# control_prg_01_10_2018.net
KiCad netlist of a schematic drawn in EAGLE
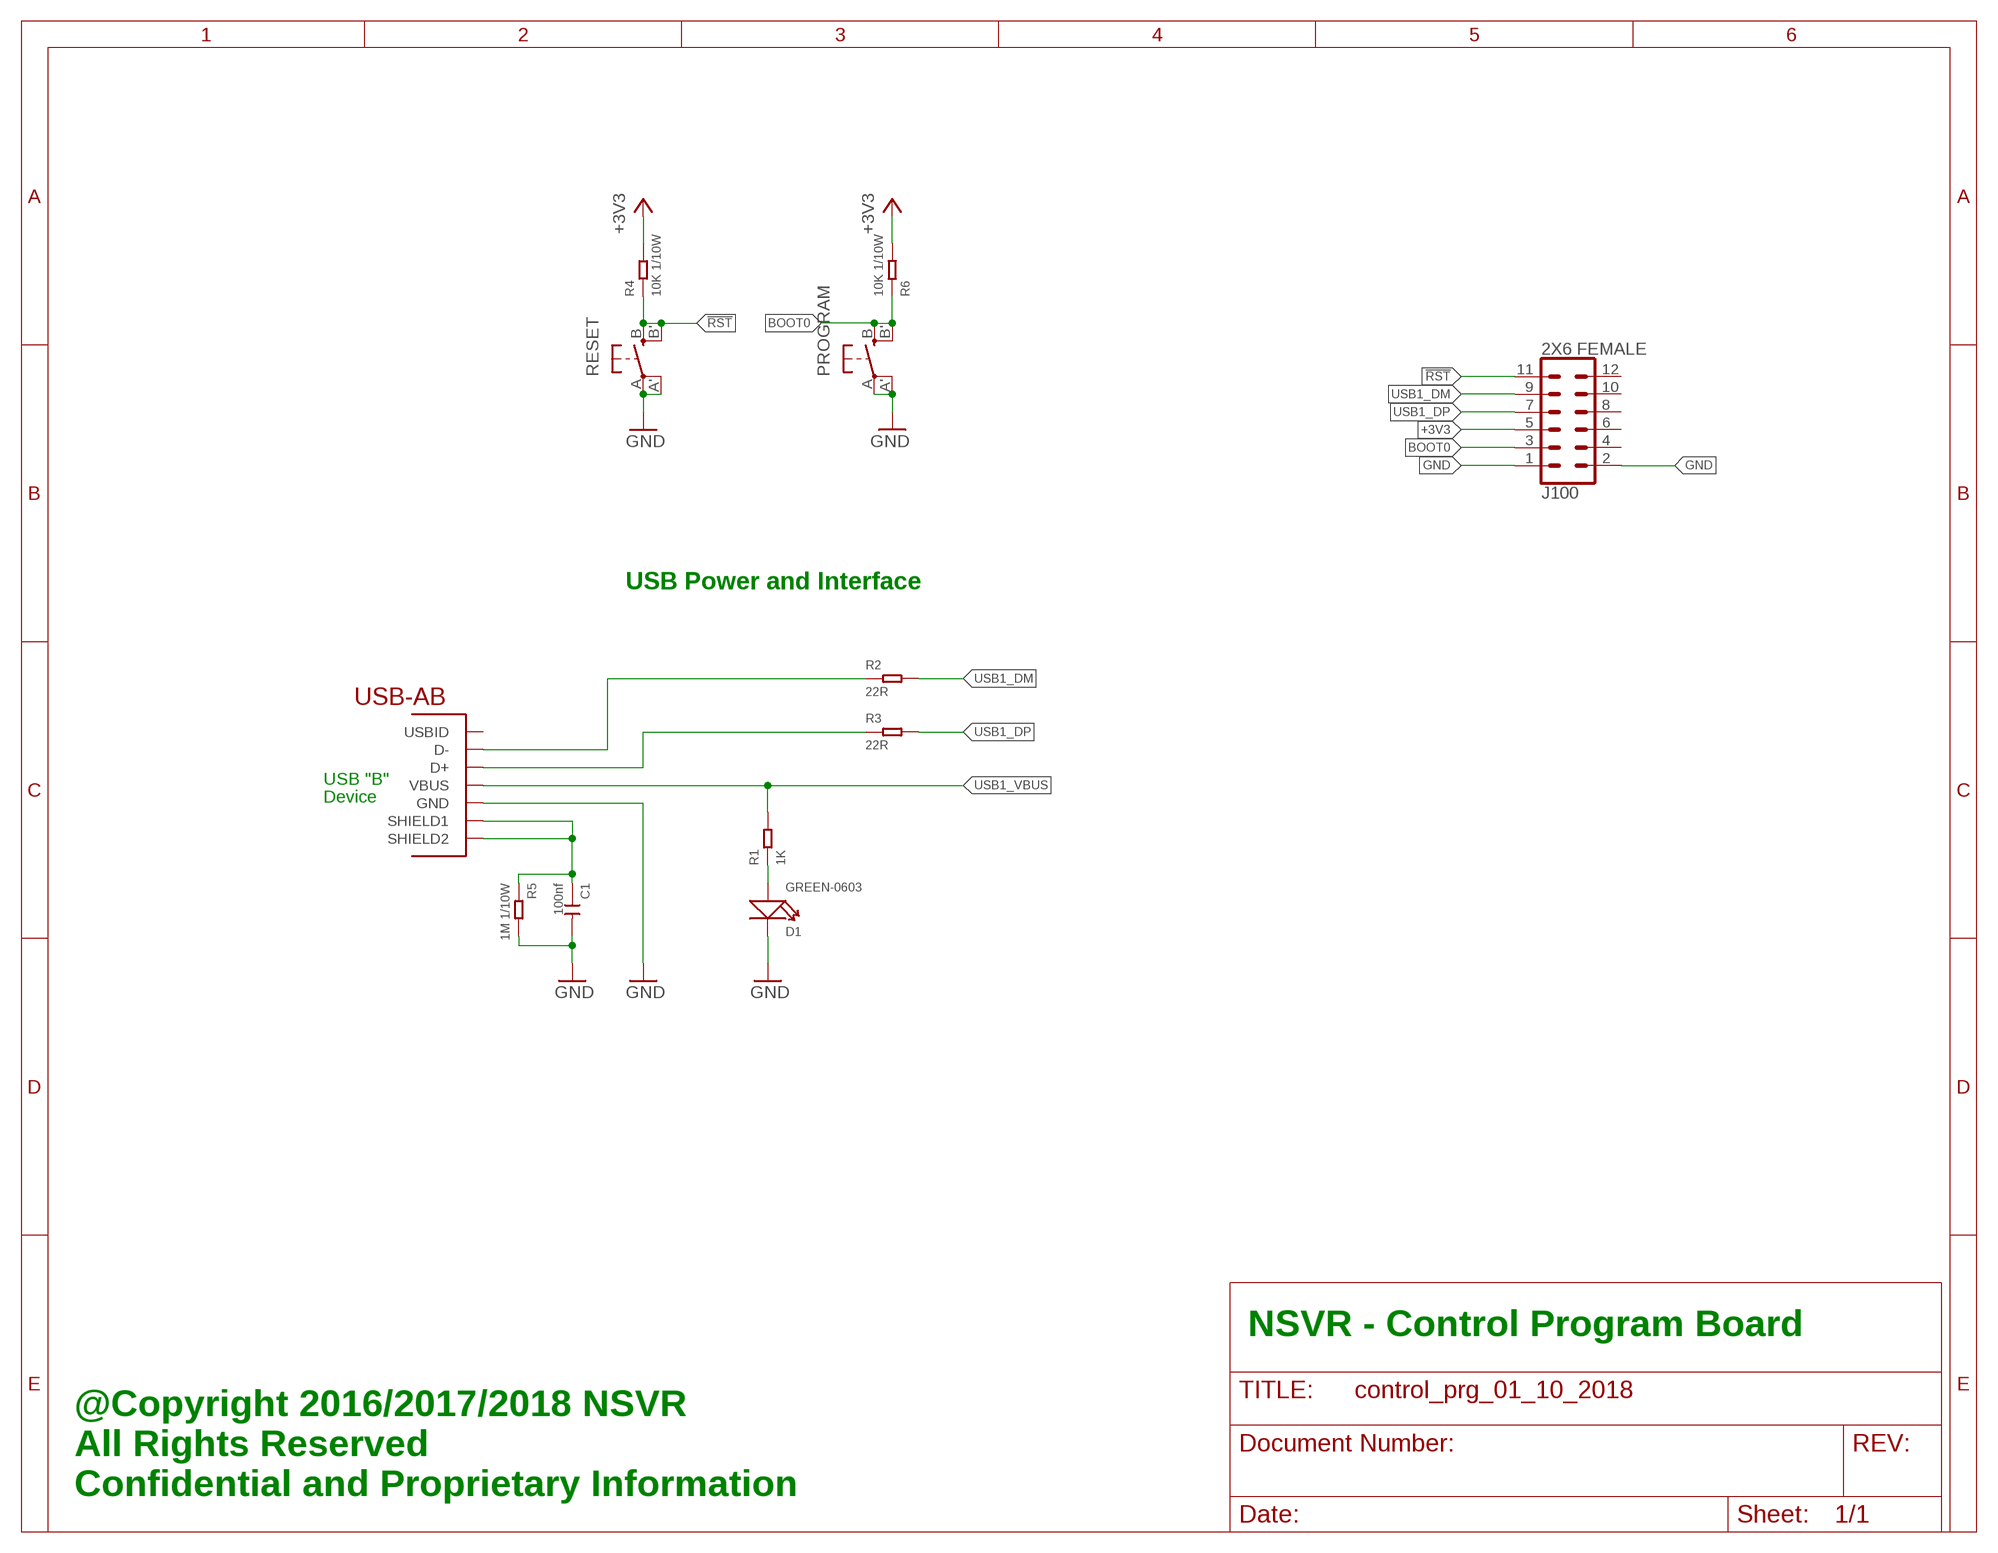
[diagram p0: schematic, sheet 1]

(export (version "E")
  (design (tool "Eeschema 10.0.6"))
  (components
    (comp (ref "C1")
      (value "100nf")
      (footprint "eagle-import:C0603")
      (fields (field (name "MPN") "CC0603KRX7R9BB104"))
      (libsource (lib "eagle-import") (part "CERAMIC-100NF-50V-10%-X7R(0603)"))
    )
    (comp (ref "D1")
      (value "GREEN-0603")
      (footprint "eagle-import:LED-0603")
      (fields (field (name "MPN") "19-217-G7C-AN1P2-3T"))
      (libsource (lib "eagle-import") (part "SMD-LED-CLEAR-GREEN(0603)"))
    )
    (comp (ref "J100")
      (value "2X6 FEMALE")
      (footprint "eagle-import:2X6")
      (libsource (lib "eagle-import") (part "CONN_06X2PTH_FEMALE"))
    )
    (comp (ref "PROGRAM")
      (value "EVQQ2")
      (footprint "eagle-import:EVQ-Q2")
      (libsource (lib "eagle-import") (part "EVQQ2"))
    )
    (comp (ref "R1")
      (value "1K")
      (footprint "eagle-import:R0603")
      (fields (field (name "MPN") "RC0603FR-071KL"))
      (libsource (lib "eagle-import") (part "SMD-RES-1K-1%-1/10W(0603)"))
    )
    (comp (ref "R2")
      (value "22R")
      (footprint "eagle-import:R0603")
      (fields (field (name "MPN") "RC0603JR-0722RL"))
      (libsource (lib "eagle-import") (part "SMD-RES-22R-5%-1/10W(0603)"))
    )
    (comp (ref "R3")
      (value "22R")
      (footprint "eagle-import:R0603")
      (fields (field (name "MPN") "RC0603JR-0722RL"))
      (libsource (lib "eagle-import") (part "SMD-RES-22R-5%-1/10W(0603)"))
    )
    (comp (ref "R4")
      (value "10K 1/10W")
      (footprint "eagle-import:R0603")
      (fields (field (name "MPN") "RC0603JR-0710KL"))
      (libsource (lib "eagle-import") (part "SMD-RES-10K-5%-1/10W(0603)"))
    )
    (comp (ref "R5")
      (value "1M 1/10W")
      (footprint "eagle-import:R0603")
      (fields (field (name "MPN") "RC0603JR-071ML"))
      (libsource (lib "eagle-import") (part "SMD-RES-1M-5%-1/10W(0603)"))
    )
    (comp (ref "R6")
      (value "10K 1/10W")
      (footprint "eagle-import:R0603")
      (fields (field (name "MPN") "RC0603JR-0710KL"))
      (libsource (lib "eagle-import") (part "SMD-RES-10K-5%-1/10W(0603)"))
    )
    (comp (ref "RESET")
      (value "EVQQ2")
      (footprint "eagle-import:EVQ-Q2")
      (libsource (lib "eagle-import") (part "EVQQ2"))
    )
    (comp (ref "USB")
      (value "USB_AB")
      (footprint "eagle-import:USB-AB-MICRO-SMD")
      (libsource (lib "eagle-import") (part "USB_AB"))
    )
  )
  (nets
    (net (code "1") (name "+3V3") (class "Default")
      (node (ref "J100") (pin "5") (pinfunction "5_5") (pintype "passive"))
      (node (ref "R4") (pin "2") (pinfunction "2_2") (pintype "passive"))
      (node (ref "R6") (pin "2") (pinfunction "2_2") (pintype "passive"))
    )
    (net (code "2") (name "/~{RST}") (class "Default")
      (node (ref "J100") (pin "11") (pinfunction "11_11") (pintype "passive"))
      (node (ref "R4") (pin "1") (pinfunction "1_1") (pintype "passive"))
      (node (ref "RESET") (pin "B") (pinfunction "S_B") (pintype "passive"))
      (node (ref "RESET") (pin "B'") (pinfunction "S1_B'") (pintype "passive"))
    )
    (net (code "3") (name "BOOT0") (class "Default")
      (node (ref "J100") (pin "3") (pinfunction "3_3") (pintype "passive"))
      (node (ref "PROGRAM") (pin "B") (pinfunction "S_B") (pintype "passive"))
      (node (ref "PROGRAM") (pin "B'") (pinfunction "S1_B'") (pintype "passive"))
      (node (ref "R6") (pin "1") (pinfunction "1_1") (pintype "passive"))
    )
    (net (code "4") (name "GND") (class "Default")
      (node (ref "C1") (pin "2") (pinfunction "2_2") (pintype "passive"))
      (node (ref "D1") (pin "-") (pinfunction "-_-") (pintype "passive"))
      (node (ref "J100") (pin "1") (pinfunction "1_1") (pintype "passive"))
      (node (ref "J100") (pin "2") (pinfunction "2_2") (pintype "passive"))
      (node (ref "PROGRAM") (pin "A") (pinfunction "P_A") (pintype "passive"))
      (node (ref "PROGRAM") (pin "A'") (pinfunction "P1_A'") (pintype "passive"))
      (node (ref "R5") (pin "2") (pinfunction "2_2") (pintype "passive"))
      (node (ref "RESET") (pin "A") (pinfunction "P_A") (pintype "passive"))
      (node (ref "RESET") (pin "A'") (pinfunction "P1_A'") (pintype "passive"))
      (node (ref "USB") (pin "GND") (pinfunction "GND_GND") (pintype "bidirectional"))
    )
    (net (code "5") (name "Net-(C1-Pad1)") (class "Default")
      (node (ref "C1") (pin "1") (pinfunction "1_1") (pintype "passive"))
      (node (ref "R5") (pin "1") (pinfunction "1_1") (pintype "passive"))
      (node (ref "USB") (pin "SHIELD1") (pinfunction "SHIELD1_SHIELD1") (pintype "bidirectional"))
      (node (ref "USB") (pin "SHIELD2") (pinfunction "SHIELD2_SHIELD2") (pintype "bidirectional"))
    )
    (net (code "6") (name "Net-(D1-Pad+)") (class "Default")
      (node (ref "D1") (pin "+") (pinfunction "+_+") (pintype "passive"))
      (node (ref "R1") (pin "1") (pinfunction "1_1") (pintype "passive"))
    )
    (net (code "7") (name "Net-(R2-Pad1)") (class "Default")
      (node (ref "R2") (pin "1") (pinfunction "1_1") (pintype "passive"))
      (node (ref "USB") (pin "D-") (pinfunction "D-_D-") (pintype "bidirectional"))
    )
    (net (code "8") (name "Net-(R3-Pad1)") (class "Default")
      (node (ref "R3") (pin "1") (pinfunction "1_1") (pintype "passive"))
      (node (ref "USB") (pin "D+") (pinfunction "D+_D+") (pintype "bidirectional"))
    )
    (net (code "9") (name "USB1_DM") (class "Default")
      (node (ref "J100") (pin "9") (pinfunction "9_9") (pintype "passive"))
      (node (ref "R2") (pin "2") (pinfunction "2_2") (pintype "passive"))
    )
    (net (code "10") (name "USB1_DP") (class "Default")
      (node (ref "J100") (pin "7") (pinfunction "7_7") (pintype "passive"))
      (node (ref "R3") (pin "2") (pinfunction "2_2") (pintype "passive"))
    )
    (net (code "11") (name "USB1_VBUS") (class "Default")
      (node (ref "R1") (pin "2") (pinfunction "2_2") (pintype "passive"))
      (node (ref "USB") (pin "VBUS") (pinfunction "VBUS_VBUS") (pintype "bidirectional"))
    )
    (net (code "12") (name "unconnected-(J100-Pad4)") (class "Default")
      (node (ref "J100") (pin "4") (pinfunction "4_4") (pintype "passive"))
    )
    (net (code "13") (name "unconnected-(J100-Pad6)") (class "Default")
      (node (ref "J100") (pin "6") (pinfunction "6_6") (pintype "passive"))
    )
    (net (code "14") (name "unconnected-(J100-Pad8)") (class "Default")
      (node (ref "J100") (pin "8") (pinfunction "8_8") (pintype "passive"))
    )
    (net (code "15") (name "unconnected-(J100-Pad10)") (class "Default")
      (node (ref "J100") (pin "10") (pinfunction "10_10") (pintype "passive"))
    )
    (net (code "16") (name "unconnected-(J100-Pad12)") (class "Default")
      (node (ref "J100") (pin "12") (pinfunction "12_12") (pintype "passive"))
    )
    (net (code "17") (name "unconnected-(USB-USBID-PadID)") (class "Default")
      (node (ref "USB") (pin "ID") (pinfunction "USBID_ID") (pintype "bidirectional"))
    )
  )
)
